# Center_panel_V1_2.net
KiCad netlist of a schematic drawn in EAGLE
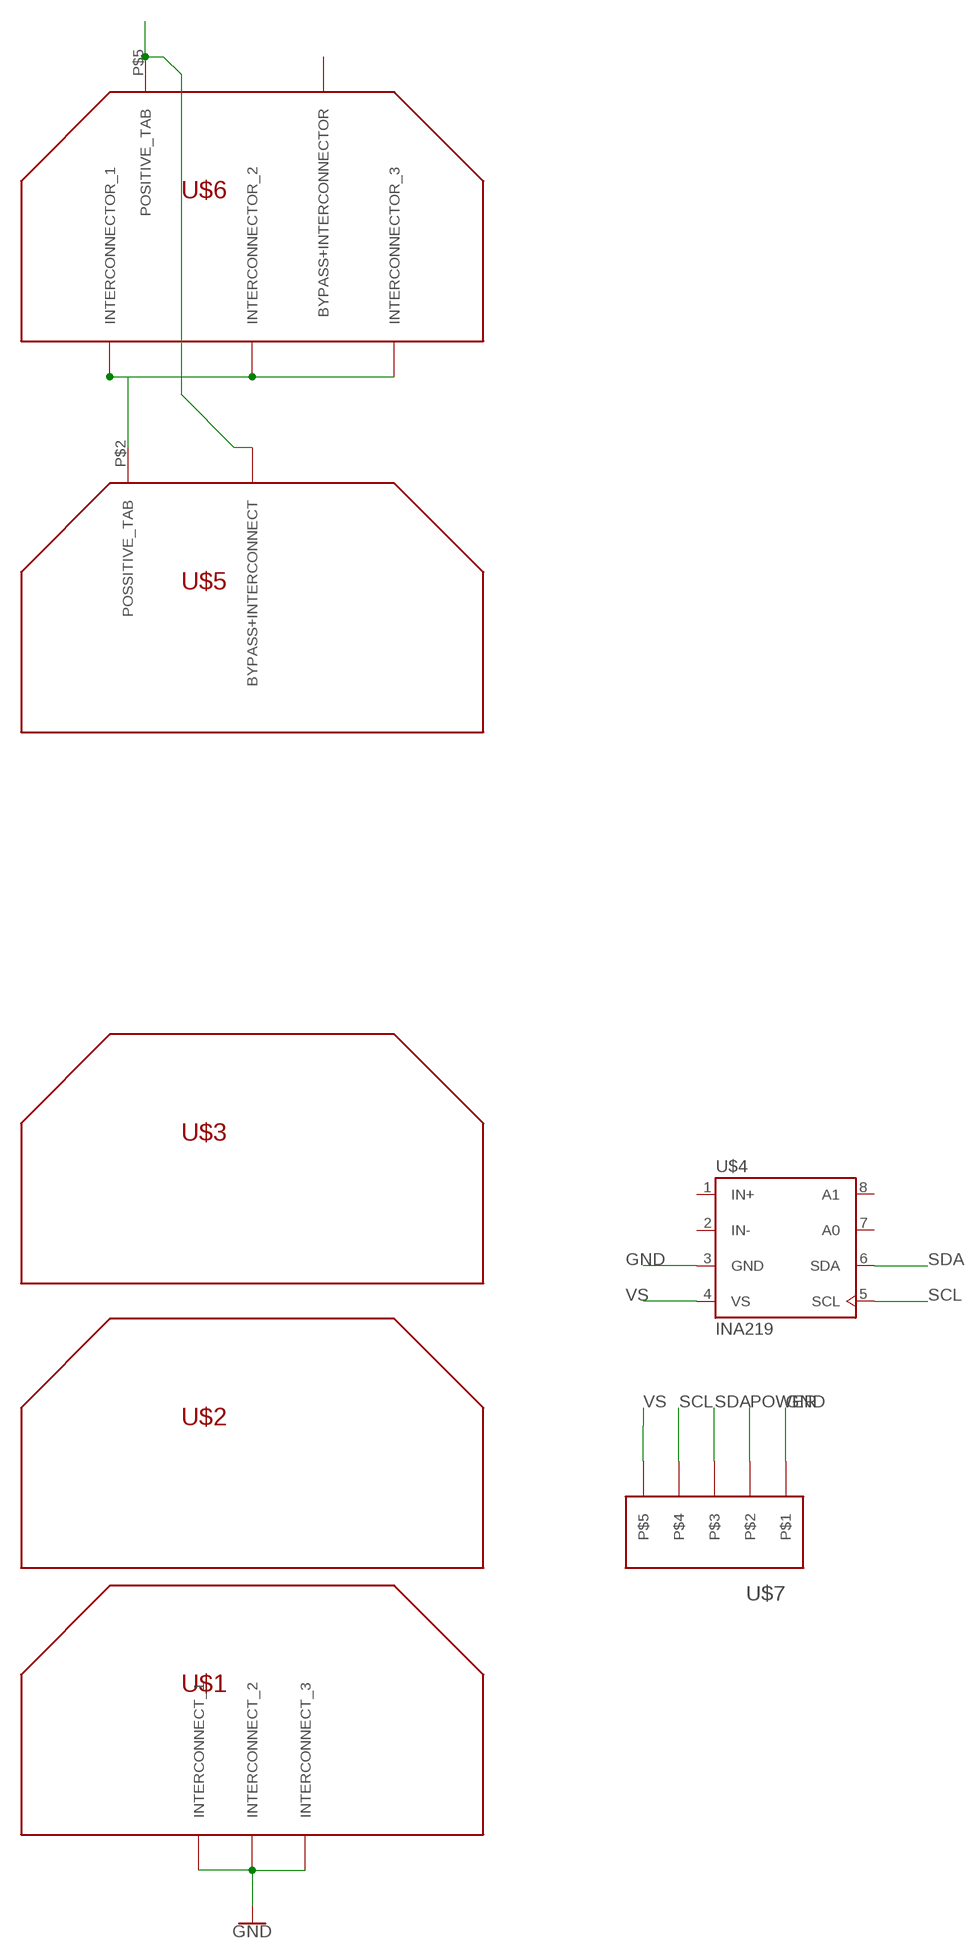
[diagram p0: schematic, sheet 1]

(export (version "E")
  (design (tool "Eeschema 10.0.6"))
  (components
    (comp (ref "U$1")
      (value "SOLAR_CELL_BOTTOM")
      (footprint "eagle-import:SOLAR_CELL_BOTTOM_SHORT-PADS")
      (libsource (lib "eagle-import") (part "SOLAR_CELL_BOTTOM"))
    )
    (comp (ref "U$2")
      (value "SOALAR_CELL_OUTLINE")
      (footprint "eagle-import:SOLAR_CELL_OUTLINE")
      (libsource (lib "eagle-import") (part "SOALAR_CELL_OUTLINE"))
    )
    (comp (ref "U$3")
      (value "SOALAR_CELL_OUTLINE")
      (footprint "eagle-import:SOLAR_CELL_OUTLINE")
      (libsource (lib "eagle-import") (part "SOALAR_CELL_OUTLINE"))
    )
    (comp (ref "U$4")
      (value "INA219")
      (footprint "eagle-import:S008")
      (libsource (lib "eagle-import") (part "INA219"))
    )
    (comp (ref "U$5")
      (value "SOLAR_CELL_TOP")
      (footprint "eagle-import:SOLAR_CELL_TOP_SHORT-PAD")
      (libsource (lib "eagle-import") (part "SOLAR_CELL_TOP"))
    )
    (comp (ref "U$6")
      (value "SOLAR_CELL_STAND-ALONE")
      (footprint "eagle-import:SOLAR_CELL_STAND-ALONE")
      (libsource (lib "eagle-import") (part "SOLAR_CELL_STAND-ALONE"))
    )
    (comp (ref "U$7")
      (value "PICOLOCK_5")
      (footprint "eagle-import:PICOLOCK_5")
      (libsource (lib "eagle-import") (part "PICOLOCK_5"))
    )
  )
  (nets
    (net (code "1") (name "/POWER") (class "Default")
      (node (ref "U$7") (pin "P$2") (pinfunction "P$2_P$2") (pintype "bidirectional"))
    )
    (net (code "2") (name "/SCL") (class "Default")
      (node (ref "U$4") (pin "5") (pinfunction "SCL_5") (pintype "input"))
      (node (ref "U$7") (pin "P$4") (pinfunction "P$4_P$4") (pintype "bidirectional"))
    )
    (net (code "3") (name "/SDA") (class "Default")
      (node (ref "U$4") (pin "6") (pinfunction "SDA_6") (pintype "output"))
      (node (ref "U$7") (pin "P$3") (pinfunction "P$3_P$3") (pintype "bidirectional"))
    )
    (net (code "4") (name "/VS") (class "Default")
      (node (ref "U$4") (pin "4") (pinfunction "VS_4") (pintype "power_in"))
      (node (ref "U$7") (pin "P$5") (pinfunction "P$5_P$5") (pintype "bidirectional"))
    )
    (net (code "5") (name "GND") (class "Default")
      (node (ref "U$1") (pin "P$1") (pinfunction "INTERCONNECT_1_P$1") (pintype "bidirectional"))
      (node (ref "U$1") (pin "P$2") (pinfunction "INTERCONNECT_2_P$2") (pintype "bidirectional"))
      (node (ref "U$1") (pin "P$3") (pinfunction "INTERCONNECT_3_P$3") (pintype "bidirectional"))
      (node (ref "U$4") (pin "3") (pinfunction "GND_3") (pintype "power_in"))
      (node (ref "U$7") (pin "P$1") (pinfunction "P$1_P$1") (pintype "bidirectional"))
    )
    (net (code "6") (name "Net-(U$5-BYPASS+INTERCONNECT)") (class "Default")
      (node (ref "U$5") (pin "P$1") (pinfunction "BYPASS+INTERCONNECT_P$1") (pintype "bidirectional"))
      (node (ref "U$6") (pin "P$5") (pinfunction "POSITIVE_TAB_P$5") (pintype "bidirectional"))
    )
    (net (code "7") (name "Net-(U$5-POSSITIVE_TAB)") (class "Default")
      (node (ref "U$5") (pin "P$2") (pinfunction "POSSITIVE_TAB_P$2") (pintype "bidirectional"))
      (node (ref "U$6") (pin "P$1") (pinfunction "INTERCONNECTOR_1_P$1") (pintype "bidirectional"))
      (node (ref "U$6") (pin "P$2") (pinfunction "INTERCONNECTOR_2_P$2") (pintype "bidirectional"))
      (node (ref "U$6") (pin "P$3") (pinfunction "INTERCONNECTOR_3_P$3") (pintype "bidirectional"))
    )
    (net (code "8") (name "unconnected-(U$4-A0-Pad7)") (class "Default")
      (node (ref "U$4") (pin "7") (pinfunction "A0_7") (pintype "input"))
    )
    (net (code "9") (name "unconnected-(U$4-A1-Pad8)") (class "Default")
      (node (ref "U$4") (pin "8") (pinfunction "A1_8") (pintype "input"))
    )
    (net (code "10") (name "unconnected-(U$4-IN+-Pad1)") (class "Default")
      (node (ref "U$4") (pin "1") (pinfunction "IN+_1") (pintype "input"))
    )
    (net (code "11") (name "unconnected-(U$4-IN--Pad2)") (class "Default")
      (node (ref "U$4") (pin "2") (pinfunction "IN-_2") (pintype "input"))
    )
    (net (code "12") (name "unconnected-(U$6-BYPASS+INTERCONNECTOR-PadP$4)") (class "Default")
      (node (ref "U$6") (pin "P$4") (pinfunction "BYPASS+INTERCONNECTOR_P$4") (pintype "bidirectional"))
    )
  )
)
